# TopSheet.net
KiCad netlist of a schematic drawn in Altium Designer
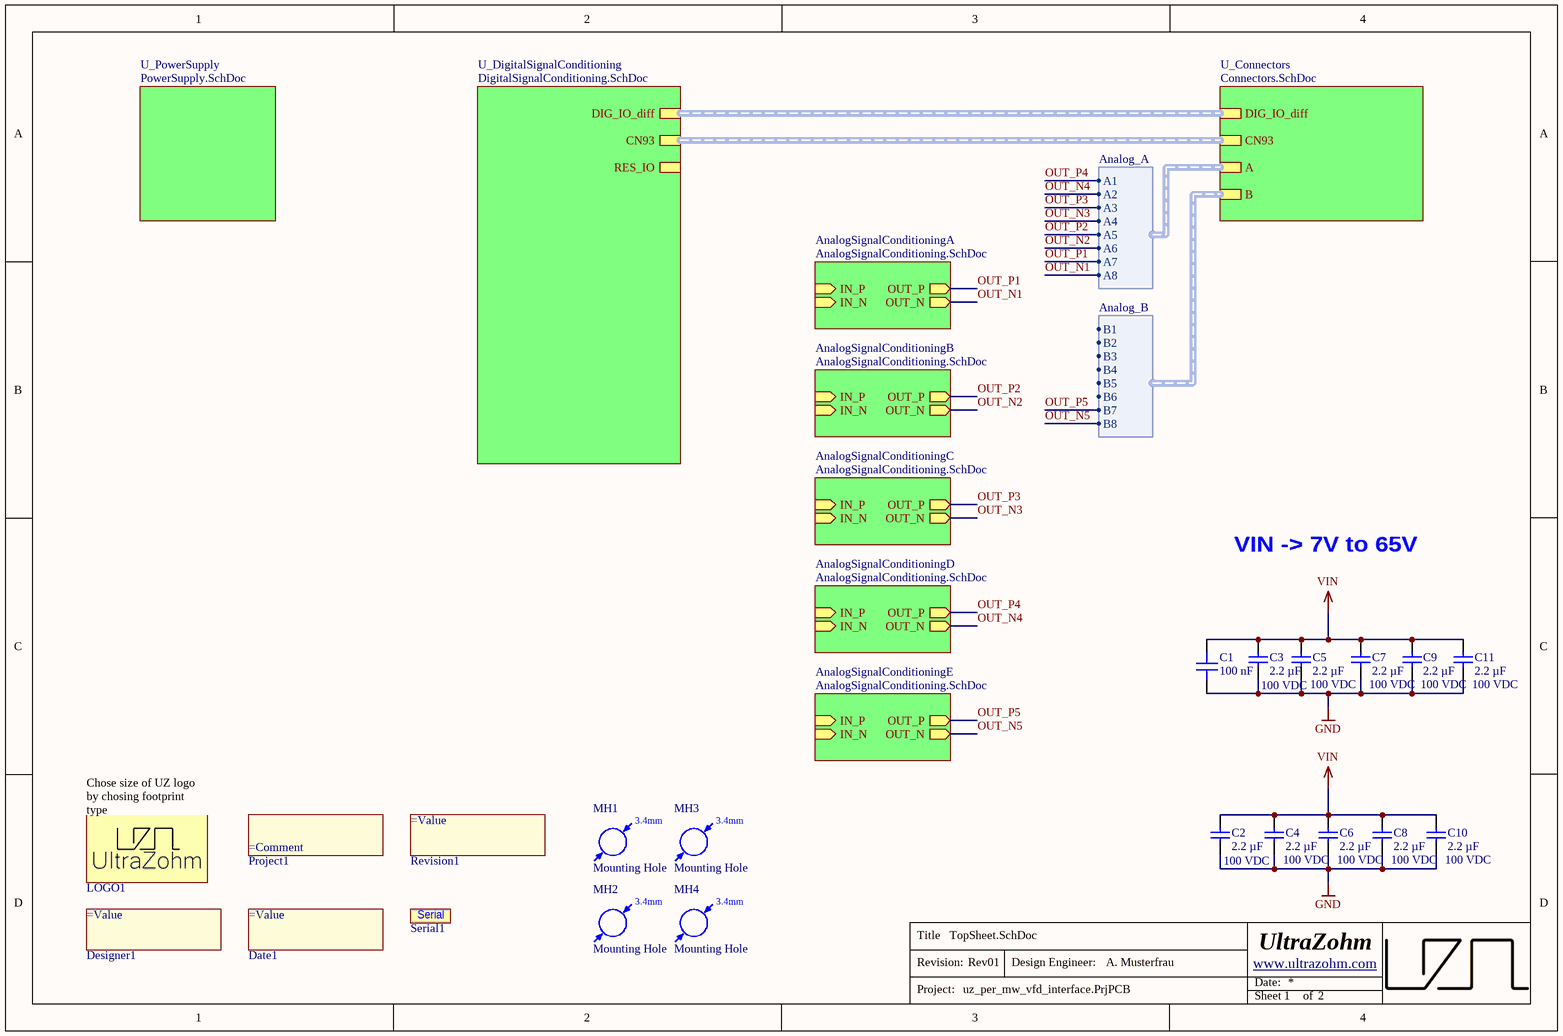
[diagram p0: TopSheet.SchDoc]

(export (version "E")
  (design (tool "Eeschema 10.0.6"))
  (components
    (comp (ref "C1")
      (value "100 nF")
      (footprint "C_0603")
      (description "100V 100nF X7S ±10% 0603 Multilayer Ceramic Capacitors MLCC - SMD/SMT ROHS")
      (fields
        (field (name "TOLERANCE") "10 %")
        (field (name "LCSC PART NUMBER") "C343025")
        (field (name "CREATED FROM") "AGeiger")
      )
      (libsource (lib "user") (part "Capacitor"))
    )
    (comp (ref "C2")
      (value "2.2 µF")
      (footprint "C_1210_TE")
      (description "100V 2.2uF X7R ±10% 1210 Multilayer Ceramic Capacitors MLCC - SMD/SMT ROHS")
      (fields
        (field (name "MANUFACTURER PART NUMBER") "FS32X225K101EGG")
        (field (name "MANUFACTURER") "PSA(Prosperity Dielectrics)")
        (field (name "VOLTAGE RATING") "100 VDC")
        (field (name "CREATED FROM") "AGeiger")
      )
      (libsource (lib "user") (part "CAP-NP"))
    )
    (comp (ref "C3")
      (value "2.2 µF")
      (footprint "C_1210_TE")
      (description "100V 2.2uF X7R ±10% 1210 Multilayer Ceramic Capacitors MLCC - SMD/SMT ROHS")
      (fields
        (field (name "MANUFACTURER PART NUMBER") "FS32X225K101EGG")
        (field (name "MANUFACTURER") "PSA(Prosperity Dielectrics)")
        (field (name "VOLTAGE RATING") "100 VDC")
        (field (name "CREATED FROM") "AGeiger")
      )
      (libsource (lib "user") (part "CAP-NP"))
    )
    (comp (ref "C4")
      (value "2.2 µF")
      (footprint "C_1210_TE")
      (description "100V 2.2uF X7R ±10% 1210 Multilayer Ceramic Capacitors MLCC - SMD/SMT ROHS")
      (fields
        (field (name "MANUFACTURER PART NUMBER") "FS32X225K101EGG")
        (field (name "MANUFACTURER") "PSA(Prosperity Dielectrics)")
        (field (name "VOLTAGE RATING") "100 VDC")
        (field (name "CREATED FROM") "AGeiger")
      )
      (libsource (lib "user") (part "CAP-NP"))
    )
    (comp (ref "C5")
      (value "2.2 µF")
      (footprint "C_1210_TE")
      (description "100V 2.2uF X7R ±10% 1210 Multilayer Ceramic Capacitors MLCC - SMD/SMT ROHS")
      (fields
        (field (name "MANUFACTURER PART NUMBER") "FS32X225K101EGG")
        (field (name "MANUFACTURER") "PSA(Prosperity Dielectrics)")
        (field (name "VOLTAGE RATING") "100 VDC")
        (field (name "CREATED FROM") "AGeiger")
      )
      (libsource (lib "user") (part "CAP-NP"))
    )
    (comp (ref "C6")
      (value "2.2 µF")
      (footprint "C_1210_TE")
      (description "100V 2.2uF X7R ±10% 1210 Multilayer Ceramic Capacitors MLCC - SMD/SMT ROHS")
      (fields
        (field (name "MANUFACTURER PART NUMBER") "FS32X225K101EGG")
        (field (name "MANUFACTURER") "PSA(Prosperity Dielectrics)")
        (field (name "VOLTAGE RATING") "100 VDC")
        (field (name "CREATED FROM") "AGeiger")
      )
      (libsource (lib "user") (part "CAP-NP"))
    )
    (comp (ref "C7")
      (value "2.2 µF")
      (footprint "C_1210_TE")
      (description "100V 2.2uF X7R ±10% 1210 Multilayer Ceramic Capacitors MLCC - SMD/SMT ROHS")
      (fields
        (field (name "MANUFACTURER PART NUMBER") "FS32X225K101EGG")
        (field (name "MANUFACTURER") "PSA(Prosperity Dielectrics)")
        (field (name "VOLTAGE RATING") "100 VDC")
        (field (name "CREATED FROM") "AGeiger")
      )
      (libsource (lib "user") (part "CAP-NP"))
    )
    (comp (ref "C8")
      (value "2.2 µF")
      (footprint "C_1210_TE")
      (description "100V 2.2uF X7R ±10% 1210 Multilayer Ceramic Capacitors MLCC - SMD/SMT ROHS")
      (fields
        (field (name "MANUFACTURER PART NUMBER") "FS32X225K101EGG")
        (field (name "MANUFACTURER") "PSA(Prosperity Dielectrics)")
        (field (name "VOLTAGE RATING") "100 VDC")
        (field (name "CREATED FROM") "AGeiger")
      )
      (libsource (lib "user") (part "CAP-NP"))
    )
    (comp (ref "C9")
      (value "2.2 µF")
      (footprint "C_1210_TE")
      (description "100V 2.2uF X7R ±10% 1210 Multilayer Ceramic Capacitors MLCC - SMD/SMT ROHS")
      (fields
        (field (name "MANUFACTURER PART NUMBER") "FS32X225K101EGG")
        (field (name "MANUFACTURER") "PSA(Prosperity Dielectrics)")
        (field (name "VOLTAGE RATING") "100 VDC")
        (field (name "CREATED FROM") "AGeiger")
      )
      (libsource (lib "user") (part "CAP-NP"))
    )
    (comp (ref "C10")
      (value "2.2 µF")
      (footprint "C_1210_TE")
      (description "100V 2.2uF X7R ±10% 1210 Multilayer Ceramic Capacitors MLCC - SMD/SMT ROHS")
      (fields
        (field (name "MANUFACTURER PART NUMBER") "FS32X225K101EGG")
        (field (name "MANUFACTURER") "PSA(Prosperity Dielectrics)")
        (field (name "VOLTAGE RATING") "100 VDC")
        (field (name "CREATED FROM") "AGeiger")
      )
      (libsource (lib "user") (part "CAP-NP"))
    )
    (comp (ref "C11")
      (value "2.2 µF")
      (footprint "C_1210_TE")
      (description "100V 2.2uF X7R ±10% 1210 Multilayer Ceramic Capacitors MLCC - SMD/SMT ROHS")
      (fields
        (field (name "MANUFACTURER PART NUMBER") "FS32X225K101EGG")
        (field (name "MANUFACTURER") "PSA(Prosperity Dielectrics)")
        (field (name "VOLTAGE RATING") "100 VDC")
        (field (name "CREATED FROM") "AGeiger")
      )
      (libsource (lib "user") (part "CAP-NP"))
    )
    (comp (ref "Date1")
      (value "~")
      (footprint "COMMENT")
      (fields
        (field (name "MANUFACTURER") "PCB Manufacturer")
        (field (name "MANUFACTURER PART NUMBER") "Project End Date")
        (field (name "CREATED FROM") "T. Wendt")
      )
      (libsource (lib "user") (part "Date"))
    )
    (comp (ref "Designer1")
      (value "~")
      (footprint "Designator:comment")
      (fields
        (field (name "MANUFACTURER") "PCB Manufacturer")
        (field (name "MANUFACTURER PART NUMBER") "Project Author")
        (field (name "CREATED FROM") "T. Wendt")
      )
      (libsource (lib "user") (part "ProjectAuthor"))
    )
    (comp (ref "LOGO1")
      (value "UZ Logo")
      (footprint "UZ_Logo_small")
      (description "Official Project Logo of the UltraZohm")
      (fields
        (field (name "MANUFACTURER") "PCB Manufacturer")
        (field (name "MANUFACTURER PART NUMBER") "UltraZohm Logo")
        (field (name "CREATED FROM") "T. Wendt")
      )
      (libsource (lib "user") (part "UZ_LOGO"))
    )
    (comp (ref "MH1")
      (value "Mounting Hole")
      (footprint "MH_3.4")
      (fields (field (name "CREATED FROM") "MHlatky"))
      (libsource (lib "user") (part "Mounting Hole"))
    )
    (comp (ref "MH2")
      (value "Mounting Hole")
      (footprint "MH_3.4")
      (fields (field (name "CREATED FROM") "MHlatky"))
      (libsource (lib "user") (part "Mounting Hole"))
    )
    (comp (ref "MH3")
      (value "Mounting Hole")
      (footprint "MH_3.4")
      (fields (field (name "CREATED FROM") "MHlatky"))
      (libsource (lib "user") (part "Mounting Hole"))
    )
    (comp (ref "MH4")
      (value "Mounting Hole")
      (footprint "MH_3.4")
      (fields (field (name "CREATED FROM") "MHlatky"))
      (libsource (lib "user") (part "Mounting Hole"))
    )
    (comp (ref "Project1")
      (value "~")
      (footprint "COMMENT")
      (fields
        (field (name "MANUFACTURER") "PCB Manufacturer")
        (field (name "MANUFACTURER PART NUMBER") "Project Name")
        (field (name "CREATED FROM") "T. Wendt")
      )
      (libsource (lib "user") (part "ProjectName"))
    )
    (comp (ref "Revision1")
      (value "~")
      (footprint "Designator:comment")
      (fields
        (field (name "MANUFACTURER") "PCB Manufacturer")
        (field (name "MANUFACTURER PART NUMBER") "Project Revision")
        (field (name "CREATED FROM") "T. Wendt")
      )
      (libsource (lib "user") (part "ProjectRevision"))
    )
    (comp (ref "Serial1")
      (value "Serial #")
      (footprint "SERIAL")
      (description "Field to put in a serial number")
      (fields
        (field (name "MANUFACTURER") "PCB Manufacturer")
        (field (name "MANUFACTURER PART NUMBER") "Serial Number")
        (field (name "CREATED FROM") "T. Wendt")
      )
      (libsource (lib "user") (part "SerialNumber"))
    )
  )
  (nets
    (net (code "28") (name "GND") (class "Default")
      (node (ref "C1") (pin "2") (pinfunction "2_2") (pintype "passive"))
      (node (ref "C10") (pin "2") (pinfunction "2_2") (pintype "passive"))
      (node (ref "C11") (pin "2") (pinfunction "2_2") (pintype "passive"))
      (node (ref "C2") (pin "2") (pinfunction "2_2") (pintype "passive"))
      (node (ref "C3") (pin "2") (pinfunction "2_2") (pintype "passive"))
      (node (ref "C4") (pin "2") (pinfunction "2_2") (pintype "passive"))
      (node (ref "C5") (pin "2") (pinfunction "2_2") (pintype "passive"))
      (node (ref "C6") (pin "2") (pinfunction "2_2") (pintype "passive"))
      (node (ref "C7") (pin "2") (pinfunction "2_2") (pintype "passive"))
      (node (ref "C8") (pin "2") (pinfunction "2_2") (pintype "passive"))
      (node (ref "C9") (pin "2") (pinfunction "2_2") (pintype "passive"))
    )
    (net (code "29") (name "VIN") (class "Default")
      (node (ref "C1") (pin "1") (pinfunction "1_1") (pintype "passive"))
      (node (ref "C10") (pin "1") (pinfunction "1_1") (pintype "passive"))
      (node (ref "C11") (pin "1") (pinfunction "1_1") (pintype "passive"))
      (node (ref "C2") (pin "1") (pinfunction "1_1") (pintype "passive"))
      (node (ref "C3") (pin "1") (pinfunction "1_1") (pintype "passive"))
      (node (ref "C4") (pin "1") (pinfunction "1_1") (pintype "passive"))
      (node (ref "C5") (pin "1") (pinfunction "1_1") (pintype "passive"))
      (node (ref "C6") (pin "1") (pinfunction "1_1") (pintype "passive"))
      (node (ref "C7") (pin "1") (pinfunction "1_1") (pintype "passive"))
      (node (ref "C8") (pin "1") (pinfunction "1_1") (pintype "passive"))
      (node (ref "C9") (pin "1") (pinfunction "1_1") (pintype "passive"))
    )
  )
)
